# EMMC_NANDFLASH_BGA153.net
KiCad netlist of a schematic drawn in Altium Designer
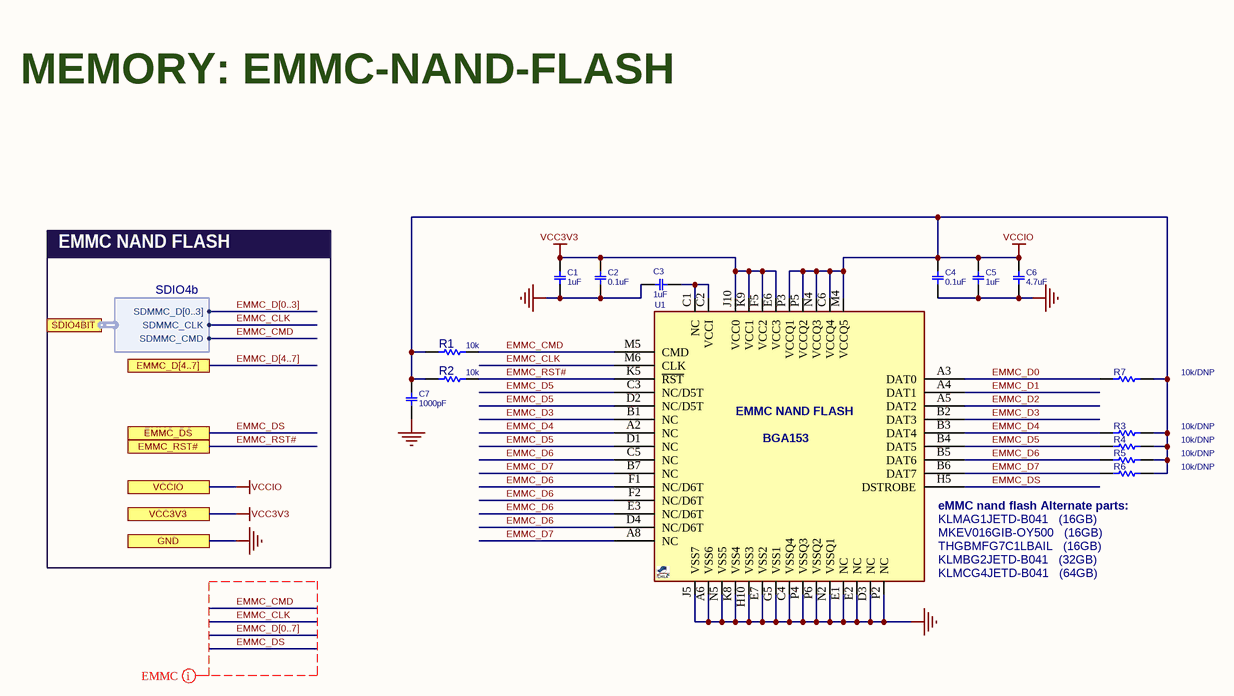
[diagram p0: EMMC_NANDFLASH_BGA153.SchDoc]

(export (version "E")
  (design (tool "Eeschema 10.0.6"))
  (components
    (comp (ref "C1")
      (value "1uF")
      (footprint "C0402")
      (description "CAP, MLCC")
      (fields (field (name "MANF_P#") "GMK105ABJ105KV-F") (field (name "MANF") "Taiyo Yuden"))
      (libsource (lib "passive_smd") (part "CAP_SMD_MLCC"))
    )
    (comp (ref "C2")
      (value "0.1uF")
      (footprint "C0402")
      (description "CAP, MLCC")
      (fields (field (name "MANF_P#") "GRM155R71H104KE14D") (field (name "MANF") "Murata"))
      (libsource (lib "passive_smd") (part "CAP_SMD_MLCC"))
    )
    (comp (ref "C3")
      (value "1uF")
      (footprint "C0402")
      (description "CAP, MLCC")
      (fields (field (name "MANF_P#") "GMK105ABJ105KV-F") (field (name "MANF") "Taiyo Yuden"))
      (libsource (lib "passive_smd") (part "CAP_SMD_MLCC"))
    )
    (comp (ref "C4")
      (value "0.1uF")
      (footprint "C0402")
      (description "CAP, MLCC")
      (fields (field (name "MANF_P#") "GRM155R71H104KE14D") (field (name "MANF") "Murata"))
      (libsource (lib "passive_smd") (part "CAP_SMD_MLCC"))
    )
    (comp (ref "C5")
      (value "1uF")
      (footprint "C0402")
      (description "CAP, MLCC")
      (fields (field (name "MANF_P#") "GMK105ABJ105KV-F") (field (name "MANF") "Taiyo Yuden"))
      (libsource (lib "passive_smd") (part "CAP_SMD_MLCC"))
    )
    (comp (ref "C6")
      (value "4.7uF")
      (footprint "C0402")
      (description "CAP, MLCC")
      (fields (field (name "MANF_P#") "LMK105BBJ475MVLF") (field (name "MANF") "Taiyo Yuden"))
      (libsource (lib "passive_smd") (part "CAP_SMD_MLCC"))
    )
    (comp (ref "C7")
      (value "1000pF")
      (footprint "C0402")
      (description "CAP, MLCC")
      (fields (field (name "MANF_P#") "CC0402JRNPO9BN102") (field (name "MANF") "Yageo"))
      (libsource (lib "mlcc_smd_passive") (part "CAP_SMD_MLCC"))
    )
    (comp (ref "R1")
      (value "10k")
      (footprint "R0402")
      (description "RESISTOR, SMD")
      (libsource (lib "passive_res_smd") (part "RES_SMD"))
    )
    (comp (ref "R2")
      (value "10k")
      (footprint "R0402")
      (description "RESISTOR, SMD")
      (libsource (lib "passive_res_smd") (part "RES_SMD"))
    )
    (comp (ref "R3")
      (value "10k/DNP")
      (footprint "R0402")
      (description "RESISTOR, SMD")
      (libsource (lib "passive_res_smd") (part "RES_SMD"))
    )
    (comp (ref "R4")
      (value "10k/DNP")
      (footprint "R0402")
      (description "RESISTOR, SMD")
      (libsource (lib "passive_res_smd") (part "RES_SMD"))
    )
    (comp (ref "R5")
      (value "10k/DNP")
      (footprint "R0402")
      (description "RESISTOR, SMD")
      (libsource (lib "passive_res_smd") (part "RES_SMD"))
    )
    (comp (ref "R6")
      (value "10k/DNP")
      (footprint "R0402")
      (description "RESISTOR, SMD")
      (libsource (lib "passive_res_smd") (part "RES_SMD"))
    )
    (comp (ref "R7")
      (value "10k/DNP")
      (footprint "R0402")
      (description "RESISTOR, SMD")
      (libsource (lib "passive_res_smd") (part "RES_SMD"))
    )
    (comp (ref "U1")
      (value "eMMC_16GB")
      (footprint "BGA50_153_EMMC")
      (description "eMMC NAND FLASH, 16GB, 128Gb (16G x 8), 153-VFBGA")
      (fields (field (name "MANF_P#") "KLMAG2GEAC-B031") (field (name "MANF") "Samsung"))
      (libsource (lib "H6") (part "KLMAG2GEAC_16GB_BGA153"))
    )
  )
  (nets
    (net (code "2") (name "/EMMC_CLK") (class "Default")
      (node (ref "U1") (pin "M6") (pinfunction "CLK_M6") (pintype "passive"))
    )
    (net (code "3") (name "/EMMC_CMD") (class "Default")
      (node (ref "R1") (pin "1") (pinfunction "1_1") (pintype "passive"))
      (node (ref "U1") (pin "M5") (pinfunction "CMD_M5") (pintype "passive"))
    )
    (net (code "4") (name "/EMMC_D0") (class "Default")
      (node (ref "R7") (pin "2") (pinfunction "2_2") (pintype "passive"))
      (node (ref "U1") (pin "A3") (pinfunction "DAT0_A3") (pintype "passive"))
    )
    (net (code "5") (name "/EMMC_D1") (class "Default")
      (node (ref "U1") (pin "A4") (pinfunction "DAT1_A4") (pintype "passive"))
    )
    (net (code "6") (name "/EMMC_D2") (class "Default")
      (node (ref "U1") (pin "A5") (pinfunction "DAT2_A5") (pintype "passive"))
    )
    (net (code "7") (name "/EMMC_D3") (class "Default")
      (node (ref "U1") (pin "B1") (pinfunction "NC_B1") (pintype "passive"))
      (node (ref "U1") (pin "B2") (pinfunction "DAT3_B2") (pintype "passive"))
    )
    (net (code "8") (name "/EMMC_D4") (class "Default")
      (node (ref "R3") (pin "2") (pinfunction "2_2") (pintype "passive"))
      (node (ref "U1") (pin "A2") (pinfunction "NC_A2") (pintype "passive"))
      (node (ref "U1") (pin "B3") (pinfunction "DAT4_B3") (pintype "passive"))
    )
    (net (code "9") (name "/EMMC_D5") (class "Default")
      (node (ref "R4") (pin "2") (pinfunction "2_2") (pintype "passive"))
      (node (ref "U1") (pin "B4") (pinfunction "DAT5_B4") (pintype "passive"))
      (node (ref "U1") (pin "C3") (pinfunction "NC/D5T_C3") (pintype "passive"))
      (node (ref "U1") (pin "D1") (pinfunction "NC_D1") (pintype "passive"))
      (node (ref "U1") (pin "D2") (pinfunction "NC/D5T_D2") (pintype "passive"))
    )
    (net (code "10") (name "/EMMC_D6") (class "Default")
      (node (ref "R5") (pin "2") (pinfunction "2_2") (pintype "passive"))
      (node (ref "U1") (pin "B5") (pinfunction "DAT6_B5") (pintype "passive"))
      (node (ref "U1") (pin "C5") (pinfunction "NC_C5") (pintype "power_in"))
      (node (ref "U1") (pin "D4") (pinfunction "NC/D6T_D4") (pintype "power_in"))
      (node (ref "U1") (pin "E3") (pinfunction "NC/D6T_E3") (pintype "power_in"))
      (node (ref "U1") (pin "F1") (pinfunction "NC/D6T_F1") (pintype "power_in"))
      (node (ref "U1") (pin "F2") (pinfunction "NC/D6T_F2") (pintype "power_in"))
    )
    (net (code "11") (name "/EMMC_D7") (class "Default")
      (node (ref "R6") (pin "2") (pinfunction "2_2") (pintype "passive"))
      (node (ref "U1") (pin "A8") (pinfunction "NC_A8") (pintype "passive"))
      (node (ref "U1") (pin "B6") (pinfunction "DAT7_B6") (pintype "passive"))
      (node (ref "U1") (pin "B7") (pinfunction "NC_B7") (pintype "passive"))
    )
    (net (code "12") (name "/EMMC_DS") (class "Default")
      (node (ref "U1") (pin "H5") (pinfunction "DSTROBE_H5") (pintype "passive"))
    )
    (net (code "16") (name "/EMMC_RST#") (class "Default")
      (node (ref "R2") (pin "1") (pinfunction "1_1") (pintype "passive"))
      (node (ref "U1") (pin "K5") (pinfunction "~{RST}_K5") (pintype "passive"))
    )
    (net (code "18") (name "GND") (class "Default")
      (node (ref "C1") (pin "1") (pinfunction "1_1") (pintype "passive"))
      (node (ref "C2") (pin "1") (pinfunction "1_1") (pintype "passive"))
      (node (ref "C3") (pin "1") (pinfunction "1_1") (pintype "passive"))
      (node (ref "C4") (pin "1") (pinfunction "1_1") (pintype "passive"))
      (node (ref "C5") (pin "1") (pinfunction "1_1") (pintype "passive"))
      (node (ref "C6") (pin "1") (pinfunction "1_1") (pintype "passive"))
      (node (ref "C7") (pin "1") (pinfunction "1_1") (pintype "passive"))
      (node (ref "U1") (pin "A6") (pinfunction "VSS6_A6") (pintype "power_in"))
      (node (ref "U1") (pin "C4") (pinfunction "VSSQ4_C4") (pintype "passive"))
      (node (ref "U1") (pin "D3") (pinfunction "NC_D3") (pintype "power_in"))
      (node (ref "U1") (pin "E1") (pinfunction "NC_E1") (pintype "power_in"))
      (node (ref "U1") (pin "E2") (pinfunction "NC_E2") (pintype "power_in"))
      (node (ref "U1") (pin "E7") (pinfunction "VSS2_E7") (pintype "power_in"))
      (node (ref "U1") (pin "G5") (pinfunction "VSS1_G5") (pintype "power_in"))
      (node (ref "U1") (pin "H10") (pinfunction "VSS3_H10") (pintype "power_in"))
      (node (ref "U1") (pin "J5") (pinfunction "VSS7_J5") (pintype "power_in"))
      (node (ref "U1") (pin "K8") (pinfunction "VSS4_K8") (pintype "power_in"))
      (node (ref "U1") (pin "N2") (pinfunction "VSSQ1_N2") (pintype "power_in"))
      (node (ref "U1") (pin "N5") (pinfunction "VSS5_N5") (pintype "power_in"))
      (node (ref "U1") (pin "P2") (pinfunction "NC_P2") (pintype "power_in"))
      (node (ref "U1") (pin "P4") (pinfunction "VSSQ3_P4") (pintype "power_in"))
      (node (ref "U1") (pin "P6") (pinfunction "VSSQ2_P6") (pintype "power_in"))
    )
    (net (code "19") (name "Net-(U1-VCCI)") (class "Default")
      (node (ref "C3") (pin "2") (pinfunction "2_2") (pintype "passive"))
      (node (ref "U1") (pin "C1") (pinfunction "NC_C1") (pintype "power_in"))
      (node (ref "U1") (pin "C2") (pinfunction "VCCI_C2") (pintype "power_in"))
    )
    (net (code "20") (name "VCC3V3") (class "Default")
      (node (ref "C1") (pin "2") (pinfunction "2_2") (pintype "passive"))
      (node (ref "C2") (pin "2") (pinfunction "2_2") (pintype "passive"))
      (node (ref "U1") (pin "E6") (pinfunction "VCC3_E6") (pintype "power_in"))
      (node (ref "U1") (pin "F5") (pinfunction "VCC2_F5") (pintype "power_in"))
      (node (ref "U1") (pin "J10") (pinfunction "VCC0_J10") (pintype "passive"))
      (node (ref "U1") (pin "K9") (pinfunction "VCC1_K9") (pintype "power_in"))
    )
    (net (code "21") (name "VCCIO") (class "Default")
      (node (ref "C4") (pin "2") (pinfunction "2_2") (pintype "passive"))
      (node (ref "C5") (pin "2") (pinfunction "2_2") (pintype "passive"))
      (node (ref "C6") (pin "2") (pinfunction "2_2") (pintype "passive"))
      (node (ref "C7") (pin "2") (pinfunction "2_2") (pintype "passive"))
      (node (ref "R1") (pin "2") (pinfunction "2_2") (pintype "passive"))
      (node (ref "R2") (pin "2") (pinfunction "2_2") (pintype "passive"))
      (node (ref "R3") (pin "1") (pinfunction "1_1") (pintype "passive"))
      (node (ref "R4") (pin "1") (pinfunction "1_1") (pintype "passive"))
      (node (ref "R5") (pin "1") (pinfunction "1_1") (pintype "passive"))
      (node (ref "R6") (pin "1") (pinfunction "1_1") (pintype "passive"))
      (node (ref "R7") (pin "1") (pinfunction "1_1") (pintype "passive"))
      (node (ref "U1") (pin "C6") (pinfunction "VCCQ4_C6") (pintype "passive"))
      (node (ref "U1") (pin "M4") (pinfunction "VCCQ5_M4") (pintype "power_in"))
      (node (ref "U1") (pin "N4") (pinfunction "VCCQ3_N4") (pintype "power_in"))
      (node (ref "U1") (pin "P3") (pinfunction "VCCQ1_P3") (pintype "power_in"))
      (node (ref "U1") (pin "P5") (pinfunction "VCCQ2_P5") (pintype "power_in"))
    )
  )
)
